# J2C_Video.net
KiCad netlist of a schematic drawn in EAGLE
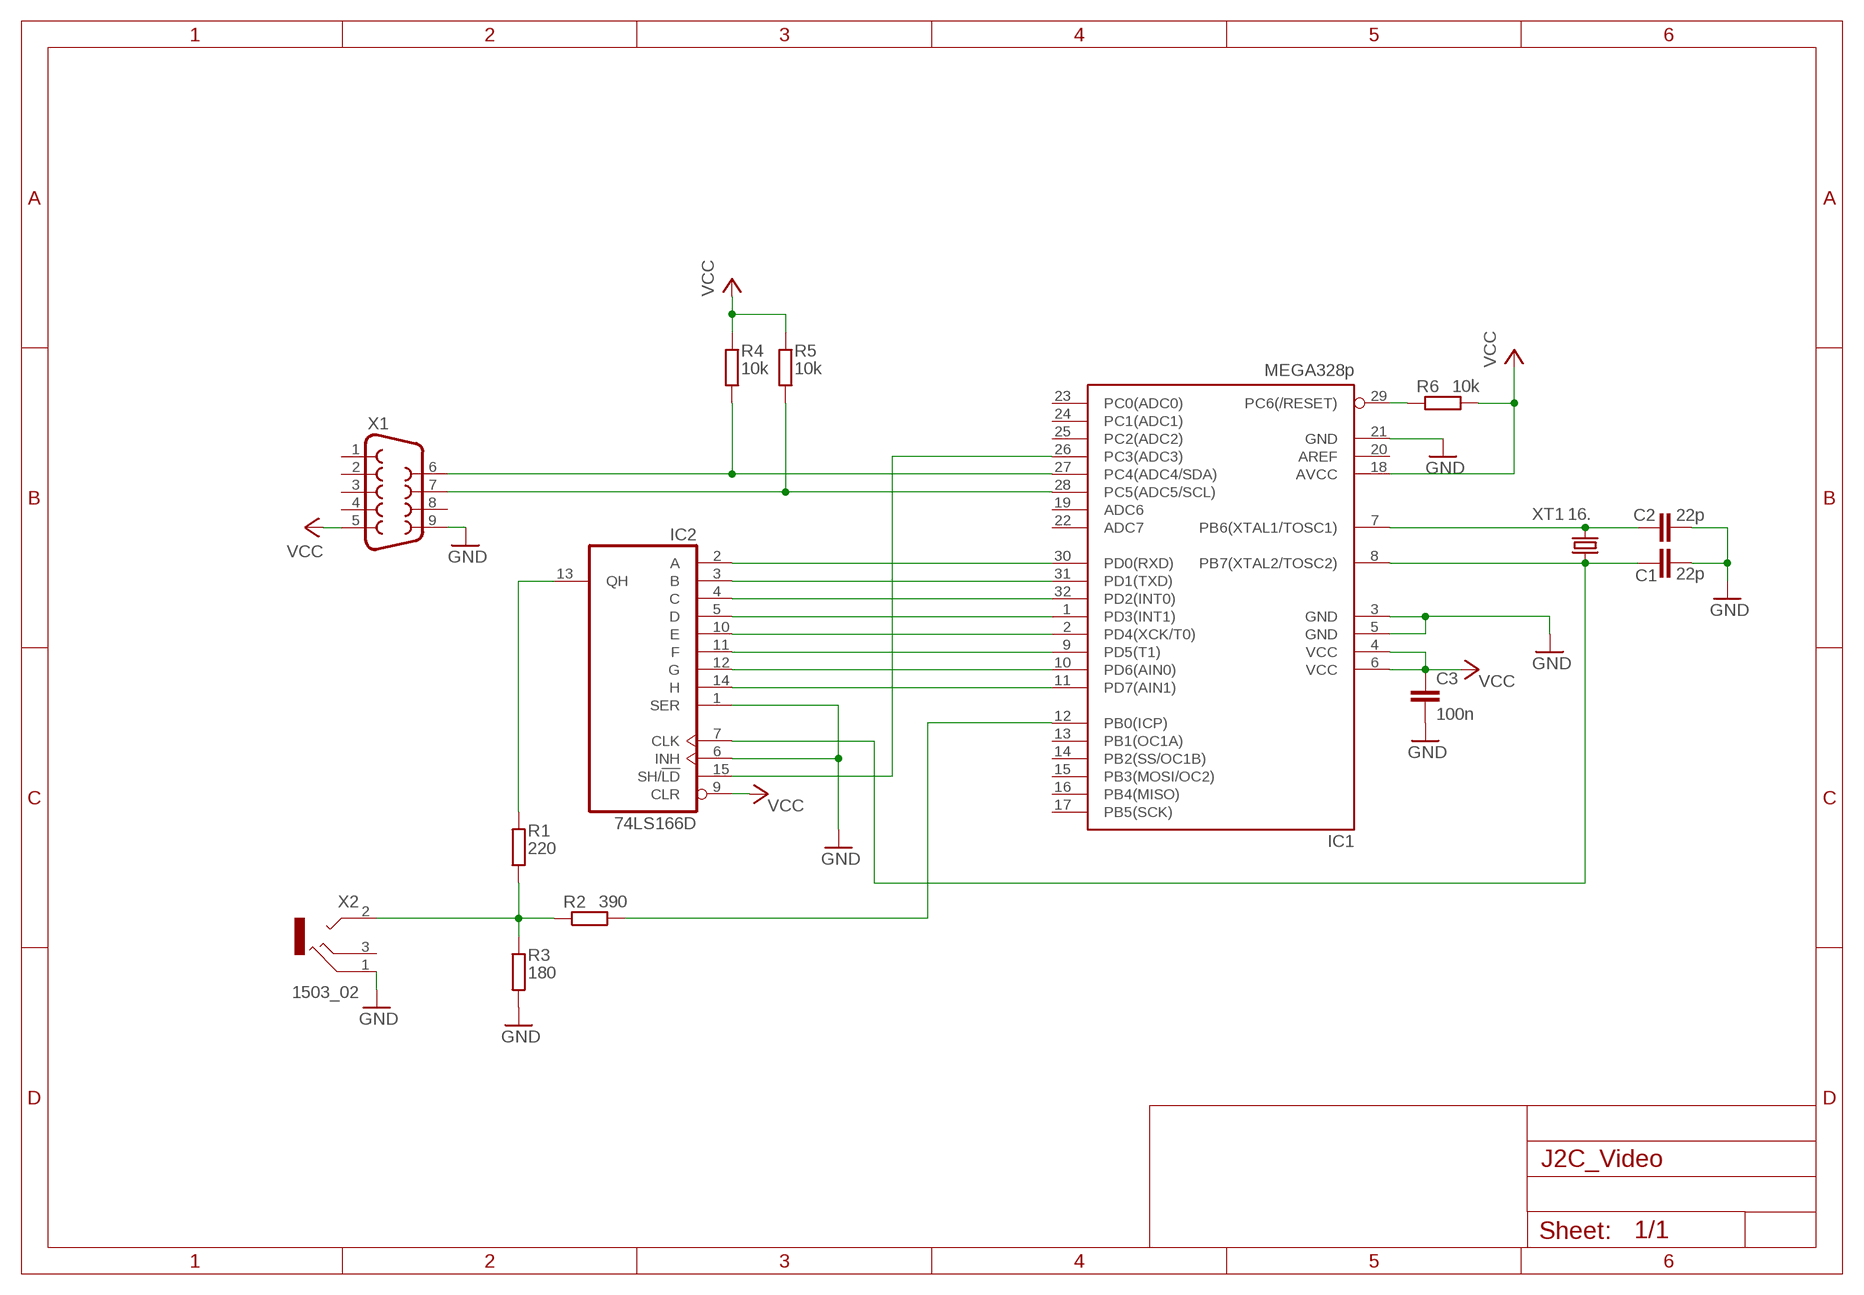
[diagram p0: schematic, sheet 1]

(export (version "E")
  (design (tool "Eeschema 10.0.6"))
  (components
    (comp (ref "C1")
      (value "22p")
      (footprint "eagle-import:C0805")
      (libsource (lib "eagle-import") (part "C-EUC0805"))
    )
    (comp (ref "C2")
      (value "22p")
      (footprint "eagle-import:C0805")
      (libsource (lib "eagle-import") (part "C-EUC0805"))
    )
    (comp (ref "C3")
      (value "100n")
      (footprint "eagle-import:C0805")
      (libsource (lib "eagle-import") (part "C-EUC0805"))
    )
    (comp (ref "IC1")
      (value "MEGA328p")
      (footprint "eagle-import:TQFP32-08")
      (fields (field (name "MPN") "ATMEGA8-16AU"))
      (libsource (lib "eagle-import") (part "MEGA8-AI"))
    )
    (comp (ref "IC2")
      (value "74LS166D")
      (footprint "eagle-import:SO16")
      (libsource (lib "eagle-import") (part "74166DLS"))
    )
    (comp (ref "R1")
      (value "220")
      (footprint "eagle-import:M0805")
      (libsource (lib "eagle-import") (part "R-EU_M0805"))
    )
    (comp (ref "R2")
      (value "390")
      (footprint "eagle-import:M0805")
      (libsource (lib "eagle-import") (part "R-EU_M0805"))
    )
    (comp (ref "R3")
      (value "180")
      (footprint "eagle-import:M0805")
      (libsource (lib "eagle-import") (part "R-EU_M0805"))
    )
    (comp (ref "R4")
      (value "10k")
      (footprint "eagle-import:M0805")
      (libsource (lib "eagle-import") (part "R-EU_M0805"))
    )
    (comp (ref "R5")
      (value "10k")
      (footprint "eagle-import:M0805")
      (libsource (lib "eagle-import") (part "R-EU_M0805"))
    )
    (comp (ref "R6")
      (value "10k")
      (footprint "eagle-import:M0805")
      (libsource (lib "eagle-import") (part "R-EU_M0805"))
    )
    (comp (ref "X1")
      (value "F09D")
      (footprint "eagle-import:F09D")
      (libsource (lib "eagle-import") (part "F09D"))
    )
    (comp (ref "X2")
      (value "1503_02")
      (footprint "eagle-import:1503_02")
      (libsource (lib "eagle-import") (part "1503_02"))
    )
    (comp (ref "XT1")
      (value "16.")
      (footprint "eagle-import:TC26V")
      (libsource (lib "eagle-import") (part "CRYSTALTC26V"))
    )
  )
  (nets
    (net (code "1") (name "GND") (class "Default")
      (node (ref "C1") (pin "2") (pinfunction "2_2") (pintype "passive"))
      (node (ref "C2") (pin "2") (pinfunction "2_2") (pintype "passive"))
      (node (ref "C3") (pin "2") (pinfunction "2_2") (pintype "passive"))
      (node (ref "IC1") (pin "21") (pinfunction "GND_21") (pintype "power_in"))
      (node (ref "IC1") (pin "3") (pinfunction "GND_3") (pintype "power_in"))
      (node (ref "IC1") (pin "5") (pinfunction "GND_5") (pintype "power_in"))
      (node (ref "IC2") (pin "1") (pinfunction "SER_1") (pintype "input"))
      (node (ref "IC2") (pin "6") (pinfunction "INH_6") (pintype "input"))
      (node (ref "R3") (pin "2") (pinfunction "2_2") (pintype "passive"))
      (node (ref "X1") (pin "9") (pinfunction "9_9") (pintype "passive"))
      (node (ref "X2") (pin "1") (pinfunction "1_1") (pintype "passive"))
    )
    (net (code "2") (name "Net-(IC1-PB0(ICP))") (class "Default")
      (node (ref "IC1") (pin "12") (pinfunction "PB0(ICP)_12") (pintype "bidirectional"))
      (node (ref "R2") (pin "2") (pinfunction "2_2") (pintype "passive"))
    )
    (net (code "3") (name "Net-(IC1-PB6(XTAL1{slash}TOSC1))") (class "Default")
      (node (ref "C2") (pin "1") (pinfunction "1_1") (pintype "passive"))
      (node (ref "IC1") (pin "7") (pinfunction "PB6(XTAL1/TOSC1)_7") (pintype "bidirectional"))
      (node (ref "XT1") (pin "2") (pinfunction "2_2") (pintype "passive"))
    )
    (net (code "4") (name "Net-(IC1-PB7(XTAL2{slash}TOSC2))") (class "Default")
      (node (ref "C1") (pin "1") (pinfunction "1_1") (pintype "passive"))
      (node (ref "IC1") (pin "8") (pinfunction "PB7(XTAL2/TOSC2)_8") (pintype "bidirectional"))
      (node (ref "IC2") (pin "7") (pinfunction "CLK_7") (pintype "input"))
      (node (ref "XT1") (pin "1") (pinfunction "1_1") (pintype "passive"))
    )
    (net (code "5") (name "Net-(IC1-PC3(ADC3))") (class "Default")
      (node (ref "IC1") (pin "26") (pinfunction "PC3(ADC3)_26") (pintype "bidirectional"))
      (node (ref "IC2") (pin "15") (pinfunction "SH/~{LD}_15") (pintype "input"))
    )
    (net (code "6") (name "Net-(IC1-PC4(ADC4{slash}SDA))") (class "Default")
      (node (ref "IC1") (pin "27") (pinfunction "PC4(ADC4/SDA)_27") (pintype "bidirectional"))
      (node (ref "R4") (pin "2") (pinfunction "2_2") (pintype "passive"))
      (node (ref "X1") (pin "6") (pinfunction "6_6") (pintype "passive"))
    )
    (net (code "7") (name "Net-(IC1-PC5(ADC5{slash}SCL))") (class "Default")
      (node (ref "IC1") (pin "28") (pinfunction "PC5(ADC5/SCL)_28") (pintype "bidirectional"))
      (node (ref "R5") (pin "2") (pinfunction "2_2") (pintype "passive"))
      (node (ref "X1") (pin "7") (pinfunction "7_7") (pintype "passive"))
    )
    (net (code "8") (name "Net-(IC1-PC6({slash}RESET))") (class "Default")
      (node (ref "IC1") (pin "29") (pinfunction "PC6(/RESET)_29") (pintype "bidirectional"))
      (node (ref "R6") (pin "1") (pinfunction "1_1") (pintype "passive"))
    )
    (net (code "9") (name "Net-(IC1-PD0(RXD))") (class "Default")
      (node (ref "IC1") (pin "30") (pinfunction "PD0(RXD)_30") (pintype "bidirectional"))
      (node (ref "IC2") (pin "2") (pinfunction "A_2") (pintype "input"))
    )
    (net (code "10") (name "Net-(IC1-PD1(TXD))") (class "Default")
      (node (ref "IC1") (pin "31") (pinfunction "PD1(TXD)_31") (pintype "bidirectional"))
      (node (ref "IC2") (pin "3") (pinfunction "B_3") (pintype "input"))
    )
    (net (code "11") (name "Net-(IC1-PD2(INT0))") (class "Default")
      (node (ref "IC1") (pin "32") (pinfunction "PD2(INT0)_32") (pintype "bidirectional"))
      (node (ref "IC2") (pin "4") (pinfunction "C_4") (pintype "input"))
    )
    (net (code "12") (name "Net-(IC1-PD3(INT1))") (class "Default")
      (node (ref "IC1") (pin "1") (pinfunction "PD3(INT1)_1") (pintype "bidirectional"))
      (node (ref "IC2") (pin "5") (pinfunction "D_5") (pintype "input"))
    )
    (net (code "13") (name "Net-(IC1-PD4(XCK{slash}T0))") (class "Default")
      (node (ref "IC1") (pin "2") (pinfunction "PD4(XCK/T0)_2") (pintype "bidirectional"))
      (node (ref "IC2") (pin "10") (pinfunction "E_10") (pintype "input"))
    )
    (net (code "14") (name "Net-(IC1-PD5(T1))") (class "Default")
      (node (ref "IC1") (pin "9") (pinfunction "PD5(T1)_9") (pintype "bidirectional"))
      (node (ref "IC2") (pin "11") (pinfunction "F_11") (pintype "input"))
    )
    (net (code "15") (name "Net-(IC1-PD6(AIN0))") (class "Default")
      (node (ref "IC1") (pin "10") (pinfunction "PD6(AIN0)_10") (pintype "bidirectional"))
      (node (ref "IC2") (pin "12") (pinfunction "G_12") (pintype "input"))
    )
    (net (code "16") (name "Net-(IC1-PD7(AIN1))") (class "Default")
      (node (ref "IC1") (pin "11") (pinfunction "PD7(AIN1)_11") (pintype "bidirectional"))
      (node (ref "IC2") (pin "14") (pinfunction "H_14") (pintype "input"))
    )
    (net (code "17") (name "Net-(IC2A-QH)") (class "Default")
      (node (ref "IC2") (pin "13") (pinfunction "QH_13") (pintype "output"))
      (node (ref "R1") (pin "2") (pinfunction "2_2") (pintype "passive"))
    )
    (net (code "18") (name "Net-(R1-Pad1)") (class "Default")
      (node (ref "R1") (pin "1") (pinfunction "1_1") (pintype "passive"))
      (node (ref "R2") (pin "1") (pinfunction "1_1") (pintype "passive"))
      (node (ref "R3") (pin "1") (pinfunction "1_1") (pintype "passive"))
      (node (ref "X2") (pin "2") (pinfunction "2_2") (pintype "passive"))
    )
    (net (code "19") (name "VCC") (class "Default")
      (node (ref "C3") (pin "1") (pinfunction "1_1") (pintype "passive"))
      (node (ref "IC1") (pin "18") (pinfunction "AVCC_18") (pintype "power_in"))
      (node (ref "IC1") (pin "4") (pinfunction "VCC_4") (pintype "power_in"))
      (node (ref "IC1") (pin "6") (pinfunction "VCC_6") (pintype "power_in"))
      (node (ref "IC2") (pin "9") (pinfunction "CLR_9") (pintype "input"))
      (node (ref "R4") (pin "1") (pinfunction "1_1") (pintype "passive"))
      (node (ref "R5") (pin "1") (pinfunction "1_1") (pintype "passive"))
      (node (ref "R6") (pin "2") (pinfunction "2_2") (pintype "passive"))
      (node (ref "X1") (pin "5") (pinfunction "5_5") (pintype "passive"))
    )
    (net (code "20") (name "unconnected-(IC1-ADC6-Pad19)") (class "Default")
      (node (ref "IC1") (pin "19") (pinfunction "ADC6_19") (pintype "bidirectional"))
    )
    (net (code "21") (name "unconnected-(IC1-ADC7-Pad22)") (class "Default")
      (node (ref "IC1") (pin "22") (pinfunction "ADC7_22") (pintype "bidirectional"))
    )
    (net (code "22") (name "unconnected-(IC1-AREF-Pad20)") (class "Default")
      (node (ref "IC1") (pin "20") (pinfunction "AREF_20") (pintype "passive"))
    )
    (net (code "23") (name "unconnected-(IC1-PB1(OC1A)-Pad13)") (class "Default")
      (node (ref "IC1") (pin "13") (pinfunction "PB1(OC1A)_13") (pintype "bidirectional"))
    )
    (net (code "24") (name "unconnected-(IC1-PB2(SS{slash}OC1B)-Pad14)") (class "Default")
      (node (ref "IC1") (pin "14") (pinfunction "PB2(SS/OC1B)_14") (pintype "bidirectional"))
    )
    (net (code "25") (name "unconnected-(IC1-PB3(MOSI{slash}OC2)-Pad15)") (class "Default")
      (node (ref "IC1") (pin "15") (pinfunction "PB3(MOSI/OC2)_15") (pintype "bidirectional"))
    )
    (net (code "26") (name "unconnected-(IC1-PB4(MISO)-Pad16)") (class "Default")
      (node (ref "IC1") (pin "16") (pinfunction "PB4(MISO)_16") (pintype "bidirectional"))
    )
    (net (code "27") (name "unconnected-(IC1-PB5(SCK)-Pad17)") (class "Default")
      (node (ref "IC1") (pin "17") (pinfunction "PB5(SCK)_17") (pintype "bidirectional"))
    )
    (net (code "28") (name "unconnected-(IC1-PC0(ADC0)-Pad23)") (class "Default")
      (node (ref "IC1") (pin "23") (pinfunction "PC0(ADC0)_23") (pintype "bidirectional"))
    )
    (net (code "29") (name "unconnected-(IC1-PC1(ADC1)-Pad24)") (class "Default")
      (node (ref "IC1") (pin "24") (pinfunction "PC1(ADC1)_24") (pintype "bidirectional"))
    )
    (net (code "30") (name "unconnected-(IC1-PC2(ADC2)-Pad25)") (class "Default")
      (node (ref "IC1") (pin "25") (pinfunction "PC2(ADC2)_25") (pintype "bidirectional"))
    )
    (net (code "31") (name "unconnected-(X1-Pad1)") (class "Default")
      (node (ref "X1") (pin "1") (pinfunction "1_1") (pintype "passive"))
    )
    (net (code "32") (name "unconnected-(X1-Pad2)") (class "Default")
      (node (ref "X1") (pin "2") (pinfunction "2_2") (pintype "passive"))
    )
    (net (code "33") (name "unconnected-(X1-Pad3)") (class "Default")
      (node (ref "X1") (pin "3") (pinfunction "3_3") (pintype "passive"))
    )
    (net (code "34") (name "unconnected-(X1-Pad4)") (class "Default")
      (node (ref "X1") (pin "4") (pinfunction "4_4") (pintype "passive"))
    )
    (net (code "35") (name "unconnected-(X1-Pad8)") (class "Default")
      (node (ref "X1") (pin "8") (pinfunction "8_8") (pintype "passive"))
    )
    (net (code "36") (name "unconnected-(X2-2-Pad2@2)") (class "Default")
      (node (ref "X2") (pin "2@2") (pinfunction "2_2@2") (pintype "passive"))
    )
    (net (code "37") (name "unconnected-(X2-Pad3)") (class "Default")
      (node (ref "X2") (pin "3") (pinfunction "3_3") (pintype "passive"))
    )
  )
)
